# pc-gen-usb-vargain.net
KiCad netlist of a schematic drawn in EAGLE
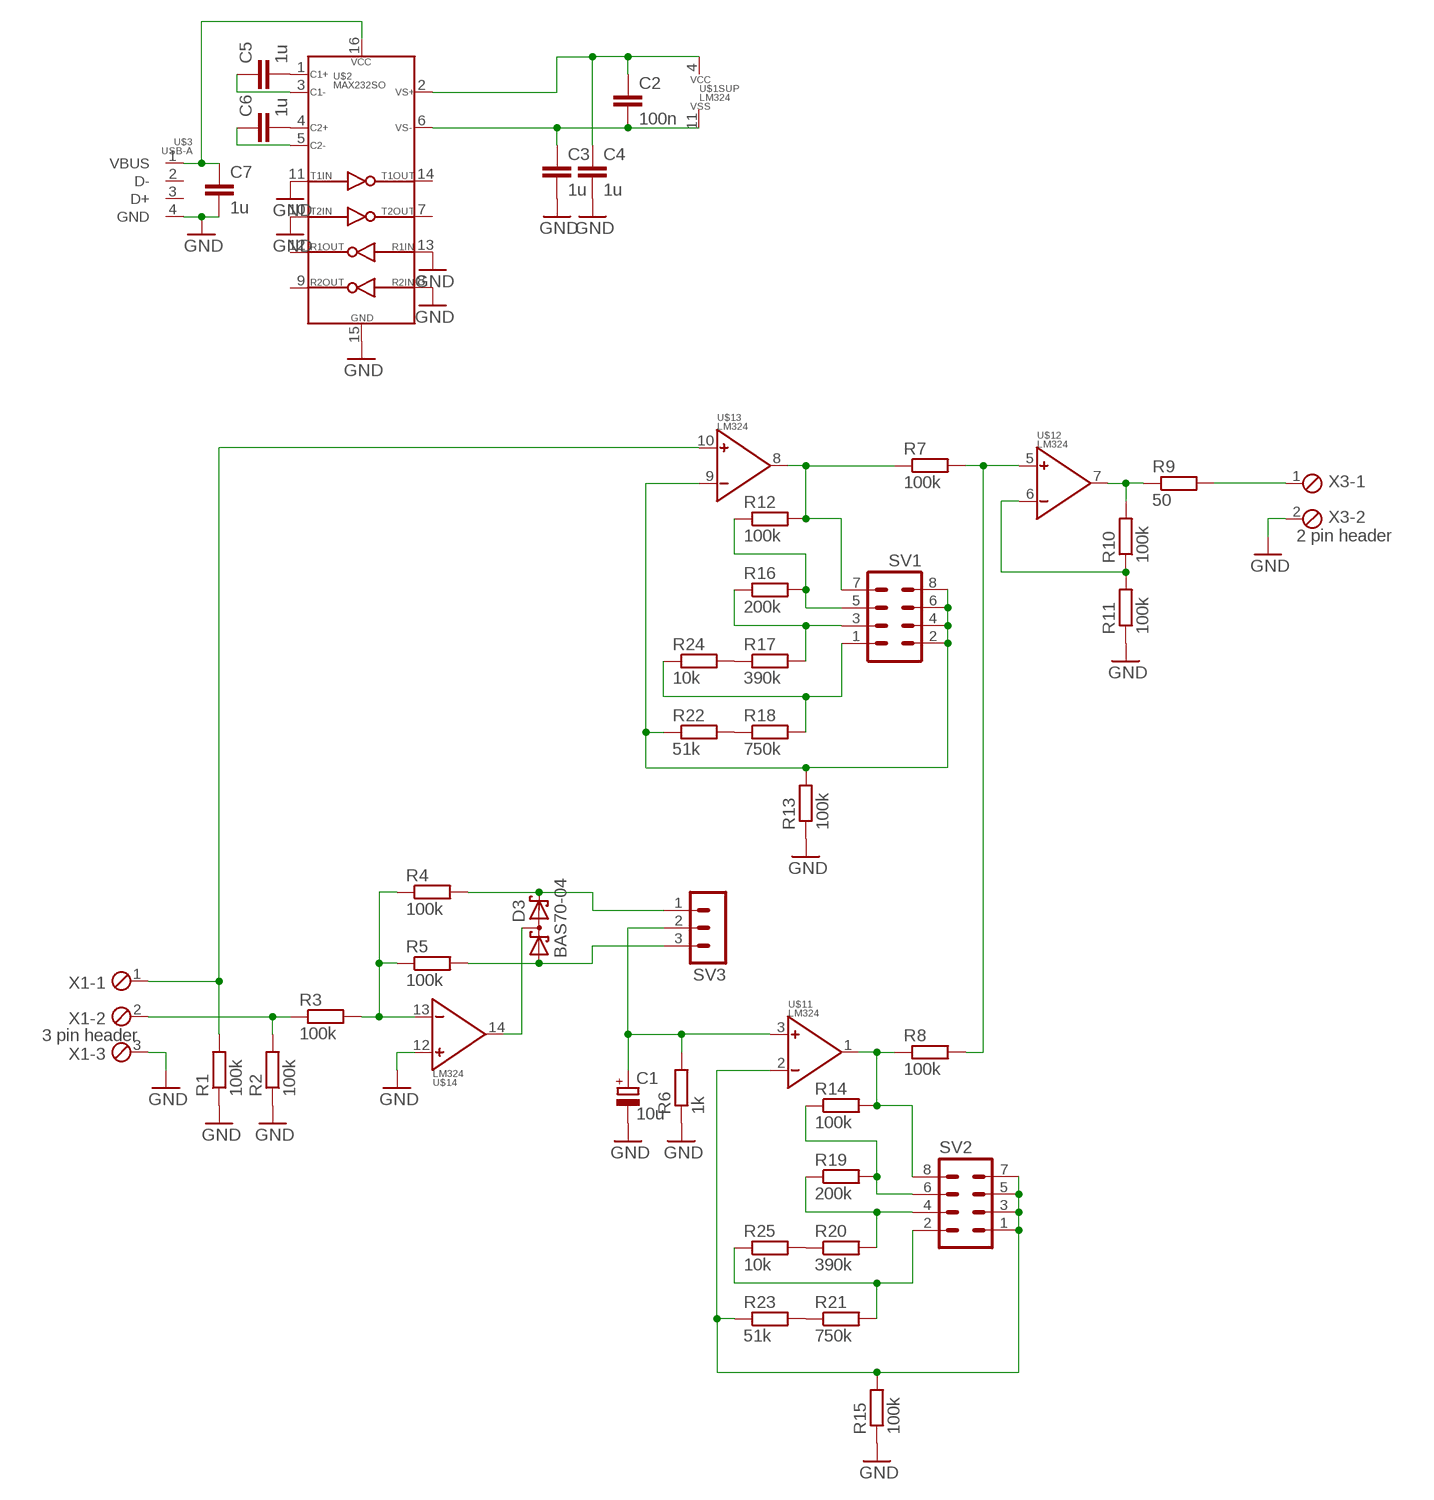
[diagram p0: schematic, sheet 1]

(export (version "E")
  (design (tool "Eeschema 10.0.6"))
  (components
    (comp (ref "C1")
      (value "10u")
      (footprint "eagle-import:E2,5-7")
      (libsource (lib "eagle-import") (part "CPOL-EUE2.5-7"))
    )
    (comp (ref "C2")
      (value "100n")
      (footprint "eagle-import:C1206")
      (libsource (lib "eagle-import") (part "C-EUC1206"))
    )
    (comp (ref "C3")
      (value "1u")
      (footprint "eagle-import:C1206")
      (libsource (lib "eagle-import") (part "C-EUC1206"))
    )
    (comp (ref "C4")
      (value "1u")
      (footprint "eagle-import:C1206")
      (libsource (lib "eagle-import") (part "C-EUC1206"))
    )
    (comp (ref "C5")
      (value "1u")
      (footprint "eagle-import:C1206")
      (libsource (lib "eagle-import") (part "C-EUC1206"))
    )
    (comp (ref "C6")
      (value "1u")
      (footprint "eagle-import:C1206")
      (libsource (lib "eagle-import") (part "C-EUC1206"))
    )
    (comp (ref "C7")
      (value "1u")
      (footprint "eagle-import:C1206")
      (libsource (lib "eagle-import") (part "C-EUC1206"))
    )
    (comp (ref "D3")
      (value "BAS70-04")
      (footprint "eagle-import:SOT23")
      (libsource (lib "eagle-import") (part "BAS70-04"))
    )
    (comp (ref "R1")
      (value "100k")
      (footprint "eagle-import:R1206")
      (libsource (lib "eagle-import") (part "R-EU_R1206"))
    )
    (comp (ref "R2")
      (value "100k")
      (footprint "eagle-import:R1206")
      (libsource (lib "eagle-import") (part "R-EU_R1206"))
    )
    (comp (ref "R3")
      (value "100k")
      (footprint "eagle-import:R1206")
      (libsource (lib "eagle-import") (part "R-EU_R1206"))
    )
    (comp (ref "R4")
      (value "100k")
      (footprint "eagle-import:R1206")
      (libsource (lib "eagle-import") (part "R-EU_R1206"))
    )
    (comp (ref "R5")
      (value "100k")
      (footprint "eagle-import:R1206")
      (libsource (lib "eagle-import") (part "R-EU_R1206"))
    )
    (comp (ref "R6")
      (value "1k")
      (footprint "eagle-import:R1206")
      (libsource (lib "eagle-import") (part "R-EU_R1206"))
    )
    (comp (ref "R7")
      (value "100k")
      (footprint "eagle-import:R1206")
      (libsource (lib "eagle-import") (part "R-EU_R1206"))
    )
    (comp (ref "R8")
      (value "100k")
      (footprint "eagle-import:R1206")
      (libsource (lib "eagle-import") (part "R-EU_R1206"))
    )
    (comp (ref "R9")
      (value "50")
      (footprint "eagle-import:R1206")
      (libsource (lib "eagle-import") (part "R-EU_R1206"))
    )
    (comp (ref "R10")
      (value "100k")
      (footprint "eagle-import:R1206")
      (libsource (lib "eagle-import") (part "R-EU_R1206"))
    )
    (comp (ref "R11")
      (value "100k")
      (footprint "eagle-import:R1206")
      (libsource (lib "eagle-import") (part "R-EU_R1206"))
    )
    (comp (ref "R12")
      (value "100k")
      (footprint "eagle-import:R1206")
      (libsource (lib "eagle-import") (part "R-EU_R1206"))
    )
    (comp (ref "R13")
      (value "100k")
      (footprint "eagle-import:R1206")
      (libsource (lib "eagle-import") (part "R-EU_R1206"))
    )
    (comp (ref "R14")
      (value "100k")
      (footprint "eagle-import:R1206")
      (libsource (lib "eagle-import") (part "R-EU_R1206"))
    )
    (comp (ref "R15")
      (value "100k")
      (footprint "eagle-import:R1206")
      (libsource (lib "eagle-import") (part "R-EU_R1206"))
    )
    (comp (ref "R16")
      (value "200k")
      (footprint "eagle-import:R1206")
      (libsource (lib "eagle-import") (part "R-EU_R1206"))
    )
    (comp (ref "R17")
      (value "390k")
      (footprint "eagle-import:R1206")
      (libsource (lib "eagle-import") (part "R-EU_R1206"))
    )
    (comp (ref "R18")
      (value "750k")
      (footprint "eagle-import:R1206")
      (libsource (lib "eagle-import") (part "R-EU_R1206"))
    )
    (comp (ref "R19")
      (value "200k")
      (footprint "eagle-import:R1206")
      (libsource (lib "eagle-import") (part "R-EU_R1206"))
    )
    (comp (ref "R20")
      (value "390k")
      (footprint "eagle-import:R1206")
      (libsource (lib "eagle-import") (part "R-EU_R1206"))
    )
    (comp (ref "R21")
      (value "750k")
      (footprint "eagle-import:R1206")
      (libsource (lib "eagle-import") (part "R-EU_R1206"))
    )
    (comp (ref "R22")
      (value "51k")
      (footprint "eagle-import:R1206")
      (libsource (lib "eagle-import") (part "R-EU_R1206"))
    )
    (comp (ref "R23")
      (value "51k")
      (footprint "eagle-import:R1206")
      (libsource (lib "eagle-import") (part "R-EU_R1206"))
    )
    (comp (ref "R24")
      (value "10k")
      (footprint "eagle-import:R1206")
      (libsource (lib "eagle-import") (part "R-EU_R1206"))
    )
    (comp (ref "R25")
      (value "10k")
      (footprint "eagle-import:R1206")
      (libsource (lib "eagle-import") (part "R-EU_R1206"))
    )
    (comp (ref "SV1")
      (value "MA04-2")
      (footprint "eagle-import:MA04-2")
      (libsource (lib "eagle-import") (part "MA04-2"))
    )
    (comp (ref "SV2")
      (value "MA04-2")
      (footprint "eagle-import:MA04-2")
      (libsource (lib "eagle-import") (part "MA04-2"))
    )
    (comp (ref "SV3")
      (value "MA03-1")
      (footprint "eagle-import:MA03-1")
      (libsource (lib "eagle-import") (part "MA03-1"))
    )
    (comp (ref "U$1")
      (value "LM324")
      (footprint "eagle-import:SO14")
      (libsource (lib "eagle-import") (part "OP-QUADSO14"))
    )
    (comp (ref "U$2")
      (value "MAX232SO")
      (footprint "eagle-import:SO16")
      (libsource (lib "eagle-import") (part "MAX232SO"))
    )
    (comp (ref "U$3")
      (value "USB-A")
      (footprint "eagle-import:USB-A")
      (libsource (lib "eagle-import") (part "USB-A"))
    )
    (comp (ref "X1")
      (value "3 pin header")
      (footprint "eagle-import:3POL254")
      (libsource (lib "eagle-import") (part "MPT3"))
    )
    (comp (ref "X3")
      (value "2 pin header")
      (footprint "eagle-import:2POL254")
      (libsource (lib "eagle-import") (part "MPT2"))
    )
  )
  (nets
    (net (code "1") (name "GND") (class "Default")
      (node (ref "C1") (pin "-") (pinfunction "-_-") (pintype "passive"))
      (node (ref "C3") (pin "2") (pinfunction "2_2") (pintype "passive"))
      (node (ref "C4") (pin "2") (pinfunction "2_2") (pintype "passive"))
      (node (ref "C7") (pin "2") (pinfunction "2_2") (pintype "passive"))
      (node (ref "R1") (pin "1") (pinfunction "1_1") (pintype "passive"))
      (node (ref "R11") (pin "1") (pinfunction "1_1") (pintype "passive"))
      (node (ref "R13") (pin "1") (pinfunction "1_1") (pintype "passive"))
      (node (ref "R15") (pin "1") (pinfunction "1_1") (pintype "passive"))
      (node (ref "R2") (pin "1") (pinfunction "1_1") (pintype "passive"))
      (node (ref "R6") (pin "1") (pinfunction "1_1") (pintype "passive"))
      (node (ref "U$1") (pin "12") (pinfunction "POS_12") (pintype "bidirectional"))
      (node (ref "U$2") (pin "10") (pinfunction "T2IN_10") (pintype "bidirectional"))
      (node (ref "U$2") (pin "11") (pinfunction "T1IN_11") (pintype "bidirectional"))
      (node (ref "U$2") (pin "13") (pinfunction "R1IN_13") (pintype "bidirectional"))
      (node (ref "U$2") (pin "15") (pinfunction "GND_15") (pintype "bidirectional"))
      (node (ref "U$2") (pin "8") (pinfunction "R2IN_8") (pintype "bidirectional"))
      (node (ref "U$3") (pin "4") (pinfunction "GND_4") (pintype "bidirectional"))
      (node (ref "X1") (pin "3") (pinfunction "1_3") (pintype "passive"))
      (node (ref "X3") (pin "2") (pinfunction "1_2") (pintype "passive"))
    )
    (net (code "2") (name "Net-(D3-A1)") (class "Default")
      (node (ref "D3") (pin "1") (pinfunction "A1_1") (pintype "passive"))
      (node (ref "R5") (pin "2") (pinfunction "2_2") (pintype "passive"))
      (node (ref "SV3") (pin "3") (pinfunction "3_3") (pintype "passive"))
    )
    (net (code "3") (name "Net-(D3-C1A2)") (class "Default")
      (node (ref "D3") (pin "3") (pinfunction "C1A2_3") (pintype "passive"))
      (node (ref "U$1") (pin "14") (pinfunction "OUT_14") (pintype "bidirectional"))
    )
    (net (code "4") (name "Net-(D3-C2)") (class "Default")
      (node (ref "D3") (pin "2") (pinfunction "C2_2") (pintype "passive"))
      (node (ref "R4") (pin "2") (pinfunction "2_2") (pintype "passive"))
      (node (ref "SV3") (pin "1") (pinfunction "1_1") (pintype "passive"))
    )
    (net (code "5") (name "Net-(R9-Pad2)") (class "Default")
      (node (ref "R9") (pin "2") (pinfunction "2_2") (pintype "passive"))
      (node (ref "X3") (pin "1") (pinfunction "1_1") (pintype "passive"))
    )
    (net (code "6") (name "Net-(R12-Pad1)") (class "Default")
      (node (ref "R12") (pin "1") (pinfunction "1_1") (pintype "passive"))
      (node (ref "R16") (pin "2") (pinfunction "2_2") (pintype "passive"))
      (node (ref "SV1") (pin "5") (pinfunction "5_5") (pintype "passive"))
    )
    (net (code "7") (name "Net-(R14-Pad1)") (class "Default")
      (node (ref "R14") (pin "1") (pinfunction "1_1") (pintype "passive"))
      (node (ref "R19") (pin "2") (pinfunction "2_2") (pintype "passive"))
      (node (ref "SV2") (pin "6") (pinfunction "6_6") (pintype "passive"))
    )
    (net (code "8") (name "Net-(R16-Pad1)") (class "Default")
      (node (ref "R16") (pin "1") (pinfunction "1_1") (pintype "passive"))
      (node (ref "R17") (pin "2") (pinfunction "2_2") (pintype "passive"))
      (node (ref "SV1") (pin "3") (pinfunction "3_3") (pintype "passive"))
    )
    (net (code "9") (name "Net-(R17-Pad1)") (class "Default")
      (node (ref "R17") (pin "1") (pinfunction "1_1") (pintype "passive"))
      (node (ref "R24") (pin "2") (pinfunction "2_2") (pintype "passive"))
    )
    (net (code "10") (name "Net-(R18-Pad1)") (class "Default")
      (node (ref "R18") (pin "1") (pinfunction "1_1") (pintype "passive"))
      (node (ref "R22") (pin "2") (pinfunction "2_2") (pintype "passive"))
    )
    (net (code "11") (name "Net-(R18-Pad2)") (class "Default")
      (node (ref "R18") (pin "2") (pinfunction "2_2") (pintype "passive"))
      (node (ref "R24") (pin "1") (pinfunction "1_1") (pintype "passive"))
      (node (ref "SV1") (pin "1") (pinfunction "1_1") (pintype "passive"))
    )
    (net (code "12") (name "Net-(R19-Pad1)") (class "Default")
      (node (ref "R19") (pin "1") (pinfunction "1_1") (pintype "passive"))
      (node (ref "R20") (pin "2") (pinfunction "2_2") (pintype "passive"))
      (node (ref "SV2") (pin "4") (pinfunction "4_4") (pintype "passive"))
    )
    (net (code "13") (name "Net-(R20-Pad1)") (class "Default")
      (node (ref "R20") (pin "1") (pinfunction "1_1") (pintype "passive"))
      (node (ref "R25") (pin "2") (pinfunction "2_2") (pintype "passive"))
    )
    (net (code "14") (name "Net-(R21-Pad1)") (class "Default")
      (node (ref "R21") (pin "1") (pinfunction "1_1") (pintype "passive"))
      (node (ref "R23") (pin "2") (pinfunction "2_2") (pintype "passive"))
    )
    (net (code "15") (name "Net-(R21-Pad2)") (class "Default")
      (node (ref "R21") (pin "2") (pinfunction "2_2") (pintype "passive"))
      (node (ref "R25") (pin "1") (pinfunction "1_1") (pintype "passive"))
      (node (ref "SV2") (pin "2") (pinfunction "2_2") (pintype "passive"))
    )
    (net (code "16") (name "Net-(U$1A-NEG)") (class "Default")
      (node (ref "R15") (pin "2") (pinfunction "2_2") (pintype "passive"))
      (node (ref "R23") (pin "1") (pinfunction "1_1") (pintype "passive"))
      (node (ref "SV2") (pin "1") (pinfunction "1_1") (pintype "passive"))
      (node (ref "SV2") (pin "3") (pinfunction "3_3") (pintype "passive"))
      (node (ref "SV2") (pin "5") (pinfunction "5_5") (pintype "passive"))
      (node (ref "SV2") (pin "7") (pinfunction "7_7") (pintype "passive"))
      (node (ref "U$1") (pin "2") (pinfunction "NEG_2") (pintype "bidirectional"))
    )
    (net (code "17") (name "Net-(U$1A-OUT)") (class "Default")
      (node (ref "R14") (pin "2") (pinfunction "2_2") (pintype "passive"))
      (node (ref "R8") (pin "1") (pinfunction "1_1") (pintype "passive"))
      (node (ref "SV2") (pin "8") (pinfunction "8_8") (pintype "passive"))
      (node (ref "U$1") (pin "1") (pinfunction "OUT_1") (pintype "bidirectional"))
    )
    (net (code "18") (name "Net-(U$1A-POS)") (class "Default")
      (node (ref "C1") (pin "+") (pinfunction "+_+") (pintype "passive"))
      (node (ref "R6") (pin "2") (pinfunction "2_2") (pintype "passive"))
      (node (ref "SV3") (pin "2") (pinfunction "2_2") (pintype "passive"))
      (node (ref "U$1") (pin "3") (pinfunction "POS_3") (pintype "bidirectional"))
    )
    (net (code "19") (name "Net-(U$1B-NEG)") (class "Default")
      (node (ref "R10") (pin "1") (pinfunction "1_1") (pintype "passive"))
      (node (ref "R11") (pin "2") (pinfunction "2_2") (pintype "passive"))
      (node (ref "U$1") (pin "6") (pinfunction "NEG_6") (pintype "bidirectional"))
    )
    (net (code "20") (name "Net-(U$1B-OUT)") (class "Default")
      (node (ref "R10") (pin "2") (pinfunction "2_2") (pintype "passive"))
      (node (ref "R9") (pin "1") (pinfunction "1_1") (pintype "passive"))
      (node (ref "U$1") (pin "7") (pinfunction "OUT_7") (pintype "bidirectional"))
    )
    (net (code "21") (name "Net-(U$1B-POS)") (class "Default")
      (node (ref "R7") (pin "2") (pinfunction "2_2") (pintype "passive"))
      (node (ref "R8") (pin "2") (pinfunction "2_2") (pintype "passive"))
      (node (ref "U$1") (pin "5") (pinfunction "POS_5") (pintype "bidirectional"))
    )
    (net (code "22") (name "Net-(U$1C-NEG)") (class "Default")
      (node (ref "R13") (pin "2") (pinfunction "2_2") (pintype "passive"))
      (node (ref "R22") (pin "1") (pinfunction "1_1") (pintype "passive"))
      (node (ref "SV1") (pin "2") (pinfunction "2_2") (pintype "passive"))
      (node (ref "SV1") (pin "4") (pinfunction "4_4") (pintype "passive"))
      (node (ref "SV1") (pin "6") (pinfunction "6_6") (pintype "passive"))
      (node (ref "SV1") (pin "8") (pinfunction "8_8") (pintype "passive"))
      (node (ref "U$1") (pin "9") (pinfunction "NEG_9") (pintype "bidirectional"))
    )
    (net (code "23") (name "Net-(U$1C-OUT)") (class "Default")
      (node (ref "R12") (pin "2") (pinfunction "2_2") (pintype "passive"))
      (node (ref "R7") (pin "1") (pinfunction "1_1") (pintype "passive"))
      (node (ref "SV1") (pin "7") (pinfunction "7_7") (pintype "passive"))
      (node (ref "U$1") (pin "8") (pinfunction "OUT_8") (pintype "bidirectional"))
    )
    (net (code "24") (name "Net-(U$1C-POS)") (class "Default")
      (node (ref "R1") (pin "2") (pinfunction "2_2") (pintype "passive"))
      (node (ref "U$1") (pin "10") (pinfunction "POS_10") (pintype "bidirectional"))
      (node (ref "X1") (pin "1") (pinfunction "1_1") (pintype "passive"))
    )
    (net (code "25") (name "Net-(U$1D-NEG)") (class "Default")
      (node (ref "R3") (pin "2") (pinfunction "2_2") (pintype "passive"))
      (node (ref "R4") (pin "1") (pinfunction "1_1") (pintype "passive"))
      (node (ref "R5") (pin "1") (pinfunction "1_1") (pintype "passive"))
      (node (ref "U$1") (pin "13") (pinfunction "NEG_13") (pintype "bidirectional"))
    )
    (net (code "26") (name "Net-(U$1E-VCC)") (class "Default")
      (node (ref "C2") (pin "1") (pinfunction "1_1") (pintype "passive"))
      (node (ref "C4") (pin "1") (pinfunction "1_1") (pintype "passive"))
      (node (ref "U$1") (pin "4") (pinfunction "VCC_4") (pintype "bidirectional"))
      (node (ref "U$2") (pin "2") (pinfunction "VS+_2") (pintype "bidirectional"))
    )
    (net (code "27") (name "Net-(U$1E-VSS)") (class "Default")
      (node (ref "C2") (pin "2") (pinfunction "2_2") (pintype "passive"))
      (node (ref "C3") (pin "1") (pinfunction "1_1") (pintype "passive"))
      (node (ref "U$1") (pin "11") (pinfunction "VSS_11") (pintype "bidirectional"))
      (node (ref "U$2") (pin "6") (pinfunction "VS-_6") (pintype "bidirectional"))
    )
    (net (code "28") (name "Net-(U$2-C1+)") (class "Default")
      (node (ref "C5") (pin "2") (pinfunction "2_2") (pintype "passive"))
      (node (ref "U$2") (pin "1") (pinfunction "C1+_1") (pintype "bidirectional"))
    )
    (net (code "29") (name "Net-(U$2-C1-)") (class "Default")
      (node (ref "C5") (pin "1") (pinfunction "1_1") (pintype "passive"))
      (node (ref "U$2") (pin "3") (pinfunction "C1-_3") (pintype "bidirectional"))
    )
    (net (code "30") (name "Net-(U$2-C2+)") (class "Default")
      (node (ref "C6") (pin "2") (pinfunction "2_2") (pintype "passive"))
      (node (ref "U$2") (pin "4") (pinfunction "C2+_4") (pintype "bidirectional"))
    )
    (net (code "31") (name "Net-(U$2-C2-)") (class "Default")
      (node (ref "C6") (pin "1") (pinfunction "1_1") (pintype "passive"))
      (node (ref "U$2") (pin "5") (pinfunction "C2-_5") (pintype "bidirectional"))
    )
    (net (code "32") (name "Net-(U$2-VCC)") (class "Default")
      (node (ref "C7") (pin "1") (pinfunction "1_1") (pintype "passive"))
      (node (ref "U$2") (pin "16") (pinfunction "VCC_16") (pintype "bidirectional"))
      (node (ref "U$3") (pin "1") (pinfunction "VBUS_1") (pintype "bidirectional"))
    )
    (net (code "33") (name "Net-(X1B-1)") (class "Default")
      (node (ref "R2") (pin "2") (pinfunction "2_2") (pintype "passive"))
      (node (ref "R3") (pin "1") (pinfunction "1_1") (pintype "passive"))
      (node (ref "X1") (pin "2") (pinfunction "1_2") (pintype "passive"))
    )
    (net (code "34") (name "unconnected-(U$2-R1OUT-Pad12)") (class "Default")
      (node (ref "U$2") (pin "12") (pinfunction "R1OUT_12") (pintype "bidirectional"))
    )
    (net (code "35") (name "unconnected-(U$2-R2OUT-Pad9)") (class "Default")
      (node (ref "U$2") (pin "9") (pinfunction "R2OUT_9") (pintype "bidirectional"))
    )
    (net (code "36") (name "unconnected-(U$2-T1OUT-Pad14)") (class "Default")
      (node (ref "U$2") (pin "14") (pinfunction "T1OUT_14") (pintype "bidirectional"))
    )
    (net (code "37") (name "unconnected-(U$2-T2OUT-Pad7)") (class "Default")
      (node (ref "U$2") (pin "7") (pinfunction "T2OUT_7") (pintype "bidirectional"))
    )
    (net (code "38") (name "unconnected-(U$3-D+-Pad3)") (class "Default")
      (node (ref "U$3") (pin "3") (pinfunction "D+_3") (pintype "bidirectional"))
    )
    (net (code "39") (name "unconnected-(U$3-D--Pad2)") (class "Default")
      (node (ref "U$3") (pin "2") (pinfunction "D-_2") (pintype "bidirectional"))
    )
  )
)
